# Sheet2.net
KiCad netlist of a schematic drawn in Altium Designer
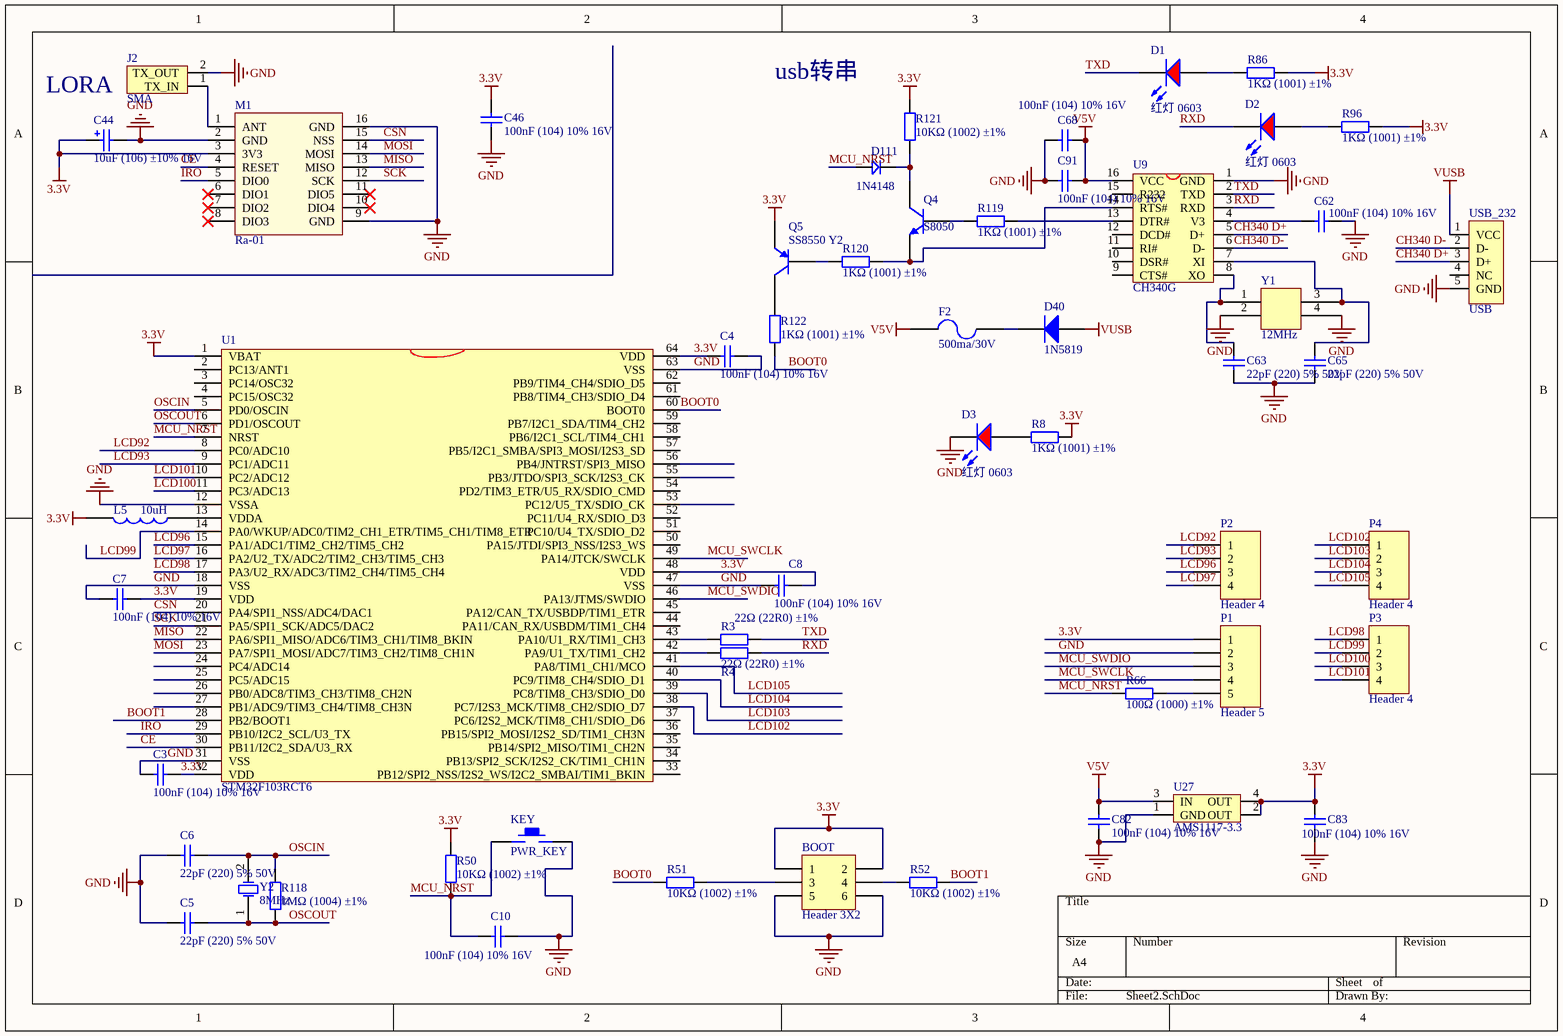
[diagram p0: Sheet2.SchDoc]

(export (version "E")
  (design (tool "Eeschema 10.0.6"))
  (components
    (comp (ref "BOOT")
      (value "Header 3X2")
      (footprint "HDR2X3")
      (description "Header, 3-Pin, Dual row")
      (fields (field (name "PUBLISHER") "Altium Limited"))
      (libsource (lib "WarShip V3 STM32103封装库") (part "Header 3X2"))
    )
    (comp (ref "C3")
      (value "100nF (104) 10% 16V")
      (footprint "0402_C")
      (description "贴片电容")
      (libsource (lib "Miscellaneous Devices LC") (part "0402 100nF (104) 10% 16V"))
    )
    (comp (ref "C4")
      (value "100nF (104) 10% 16V")
      (footprint "0402_C")
      (description "贴片电容")
      (libsource (lib "Miscellaneous Devices LC") (part "0402 100nF (104) 10% 16V"))
    )
    (comp (ref "C5")
      (value "22pF (220) 5% 50V")
      (footprint "0402_C")
      (description "贴片电容")
      (libsource (lib "Miscellaneous Devices LC") (part "0402 22pF (220) 5% 50V"))
    )
    (comp (ref "C6")
      (value "22pF (220) 5% 50V")
      (footprint "0402_C")
      (description "贴片电容")
      (libsource (lib "Miscellaneous Devices LC") (part "0402 22pF (220) 5% 50V"))
    )
    (comp (ref "C7")
      (value "100nF (104) 10% 16V")
      (footprint "0402_C")
      (description "贴片电容")
      (libsource (lib "Miscellaneous Devices LC") (part "0402 100nF (104) 10% 16V"))
    )
    (comp (ref "C8")
      (value "100nF (104) 10% 16V")
      (footprint "0402_C")
      (description "贴片电容")
      (libsource (lib "Miscellaneous Devices LC") (part "0402 100nF (104) 10% 16V"))
    )
    (comp (ref "C10")
      (value "100nF (104) 10% 16V")
      (footprint "0402_C")
      (description "贴片电容")
      (libsource (lib "Miscellaneous Devices LC") (part "0402 100nF (104) 10% 16V"))
    )
    (comp (ref "C44")
      (value "10uF (106) ±10% 16V")
      (footprint "CASE-A_3216")
      (description "钽电容")
      (libsource (lib "Miscellaneous Devices LC") (part "3216 10uF (106) 10% 16V"))
    )
    (comp (ref "C46")
      (value "100nF (104) 10% 16V")
      (footprint "0402_C")
      (description "贴片电容")
      (libsource (lib "Miscellaneous Devices LC") (part "0402 100nF (104) 10% 16V"))
    )
    (comp (ref "C62")
      (value "100nF (104) 10% 16V")
      (footprint "0402_C")
      (description "贴片电容")
      (libsource (lib "Miscellaneous Devices LC") (part "0402 100nF (104) 10% 16V"))
    )
    (comp (ref "C63")
      (value "22pF (220) 5% 50V")
      (footprint "0402_C")
      (description "贴片电容")
      (libsource (lib "Miscellaneous Devices LC") (part "0402 22pF (220) 5% 50V"))
    )
    (comp (ref "C65")
      (value "22pF (220) 5% 50V")
      (footprint "0402_C")
      (description "贴片电容")
      (libsource (lib "Miscellaneous Devices LC") (part "0402 22pF (220) 5% 50V"))
    )
    (comp (ref "C68")
      (value "100nF (104) 10% 16V")
      (footprint "0402_C")
      (description "贴片电容")
      (libsource (lib "Miscellaneous Devices LC") (part "0402 100nF (104) 10% 16V"))
    )
    (comp (ref "C82")
      (value "100nF (104) 10% 16V")
      (footprint "0402_C")
      (description "贴片电容")
      (libsource (lib "Miscellaneous Devices LC") (part "0402 100nF (104) 10% 16V"))
    )
    (comp (ref "C83")
      (value "100nF (104) 10% 16V")
      (footprint "0402_C")
      (description "贴片电容")
      (libsource (lib "Miscellaneous Devices LC") (part "0402 100nF (104) 10% 16V"))
    )
    (comp (ref "C91")
      (value "100nF (104) 10% 16V")
      (footprint "0402_C")
      (description "贴片电容")
      (libsource (lib "Miscellaneous Devices LC") (part "0402 100nF (104) 10% 16V"))
    )
    (comp (ref "D1")
      (value "红灯 0603")
      (footprint "0603_LED_S1")
      (description "发光二极管")
      (libsource (lib "Miscellaneous Devices LC") (part "0603 红灯"))
    )
    (comp (ref "D2")
      (value "红灯 0603")
      (footprint "0603_LED_S1")
      (description "发光二极管")
      (libsource (lib "Miscellaneous Devices LC") (part "0603 红灯"))
    )
    (comp (ref "D3")
      (value "红灯 0603")
      (footprint "0603_LED_S1")
      (description "发光二极管")
      (libsource (lib "Miscellaneous Devices LC") (part "0603 红灯"))
    )
    (comp (ref "D40")
      (value "1N5819")
      (footprint "LED-3528")
      (description "1 Amp General Purpose Rectifier")
      (fields (field (name "PUBLISHER") "Altium Limited"))
      (libsource (lib "*") (part "Diode 1N4001"))
    )
    (comp (ref "D111")
      (value "1N4148")
      (footprint "DIODE_SOP")
      (libsource (lib "WarShip V3 STM32103封装库") (part "D"))
    )
    (comp (ref "F2")
      (value "500ma/30V")
      (footprint "1812")
      (description "Fuse")
      (libsource (lib "*") (part "FUSE2"))
    )
    (comp (ref "J2")
      (value "SMA")
      (footprint "SMA-2")
      (description "SMA-2")
      (libsource (lib "ATK-SIM800C") (part "SMA-2"))
    )
    (comp (ref "KEY") (value "PWR_KEY") (libsource (lib "ATK-SIM800C") (part "KEY_M")))
    (comp (ref "L5") (value "10uH") (footprint "0805_L") (libsource (lib "*") (part "INDUCTOR1")))
    (comp (ref "M1")
      (value "Ra-01")
      (footprint "Ra-01 Module")
      (libsource (lib "Ra-01 Module") (part "Ra-01 Module"))
    )
    (comp (ref "P1")
      (value "Header 5")
      (footprint "HDR1X5")
      (description "Header, 5-Pin")
      (fields (field (name "PUBLISHER") "Altium Limited"))
      (libsource (lib "Miscellaneous Connectors") (part "Header 5"))
    )
    (comp (ref "P2")
      (value "Header 4")
      (footprint "HDR1X4")
      (description "Header, 4-Pin")
      (fields (field (name "PUBLISHER") "Altium Limited"))
      (libsource (lib "WarShip V3 STM32103封装库") (part "Header 4"))
    )
    (comp (ref "P3")
      (value "Header 4")
      (footprint "HDR1X4")
      (description "Header, 4-Pin")
      (fields (field (name "PUBLISHER") "Altium Limited"))
      (libsource (lib "WarShip V3 STM32103封装库") (part "Header 4"))
    )
    (comp (ref "P4")
      (value "Header 4")
      (footprint "HDR1X4")
      (description "Header, 4-Pin")
      (fields (field (name "PUBLISHER") "Altium Limited"))
      (libsource (lib "WarShip V3 STM32103封装库") (part "Header 4"))
    )
    (comp (ref "Q4")
      (value "S8050")
      (footprint "SOT-23R")
      (description "NPN Bipolar Transistor")
      (fields (field (name "PUBLISHER") "Altium Limited"))
      (libsource (lib "Miscellaneous Devices") (part "QNPN"))
    )
    (comp (ref "Q5")
      (value "SS8550 Y2")
      (footprint "SOT-23(SOT-23-3)")
      (description "三极管")
      (libsource (lib "Miscellaneous Devices LC") (part "SOT-23 SS8550 Y2"))
    )
    (comp (ref "R3")
      (value "22Ω (22R0) ±1%")
      (footprint "0402_R")
      (description "贴片电阻")
      (libsource (lib "Miscellaneous Devices LC") (part "0402 22Ω (22R0) 1%"))
    )
    (comp (ref "R4")
      (value "22Ω (22R0) ±1%")
      (footprint "0402_R")
      (description "贴片电阻")
      (libsource (lib "Miscellaneous Devices LC") (part "0402 22Ω (22R0) 1%"))
    )
    (comp (ref "R8")
      (value "1KΩ (1001) ±1%")
      (footprint "0402_R")
      (description "贴片电阻")
      (libsource (lib "Miscellaneous Devices LC") (part "0402 1KΩ (1001) 1%"))
    )
    (comp (ref "R50")
      (value "10KΩ (1002) ±1%")
      (footprint "0402_R")
      (description "贴片电阻")
      (libsource (lib "Miscellaneous Devices LC") (part "0402 10KΩ (1002) 1%"))
    )
    (comp (ref "R51")
      (value "10KΩ (1002) ±1%")
      (footprint "0402_R")
      (description "贴片电阻")
      (libsource (lib "") (part "0402 10KΩ (1002) 1%_1"))
    )
    (comp (ref "R52")
      (value "10KΩ (1002) ±1%")
      (footprint "0402_R")
      (description "贴片电阻")
      (libsource (lib "") (part "0402 10KΩ (1002) 1%_1"))
    )
    (comp (ref "R66")
      (value "100Ω (1000) ±1%")
      (footprint "0402_R")
      (description "贴片电阻")
      (libsource (lib "Miscellaneous Devices LC") (part "0402 100Ω (1000) 1%"))
    )
    (comp (ref "R86")
      (value "1KΩ (1001) ±1%")
      (footprint "0402_R")
      (description "贴片电阻")
      (libsource (lib "Miscellaneous Devices LC") (part "0402 1KΩ (1001) 1%"))
    )
    (comp (ref "R96")
      (value "1KΩ (1001) ±1%")
      (footprint "0402_R")
      (description "贴片电阻")
      (libsource (lib "Miscellaneous Devices LC") (part "0402 1KΩ (1001) 1%"))
    )
    (comp (ref "R118")
      (value "1MΩ (1004) ±1%")
      (footprint "0402_R")
      (description "贴片电阻")
      (libsource (lib "Miscellaneous Devices LC") (part "0402 1MΩ (1004) 1%"))
    )
    (comp (ref "R119")
      (value "1KΩ (1001) ±1%")
      (footprint "0402_R")
      (description "贴片电阻")
      (libsource (lib "Miscellaneous Devices LC") (part "0402 1KΩ (1001) 1%"))
    )
    (comp (ref "R120")
      (value "1KΩ (1001) ±1%")
      (footprint "0402_R")
      (description "贴片电阻")
      (libsource (lib "Miscellaneous Devices LC") (part "0402 1KΩ (1001) 1%"))
    )
    (comp (ref "R121")
      (value "10KΩ (1002) ±1%")
      (footprint "0402_R")
      (description "贴片电阻")
      (libsource (lib "Miscellaneous Devices LC") (part "0402 10KΩ (1002) 1%"))
    )
    (comp (ref "R122")
      (value "1KΩ (1001) ±1%")
      (footprint "0402_R")
      (description "贴片电阻")
      (libsource (lib "") (part "0402 1KΩ (1001) 1%_1"))
    )
    (comp (ref "U1")
      (value "STM32F103RCT6")
      (footprint "LQFP-64_10x10x05P")
      (libsource (lib "MiniSTM32 V3.0封装库") (part "STM32F103RDT6"))
    )
    (comp (ref "U9")
      (value "CH340G")
      (footprint "SOP16M")
      (description "USB2UART")
      (libsource (lib "阿波罗STM32F4&F7底板封装库") (part "CH340G"))
    )
    (comp (ref "U27")
      (value "AMS1117-3.3")
      (footprint "AMS1117")
      (libsource (lib "阿波罗STM32F4&F7底板封装库") (part "AMS1117"))
    )
    (comp (ref "USB_232")
      (value "USB")
      (footprint "USB（公）:PCBComponent_1")
      (libsource (lib "WarShip V3 STM32103封装库") (part "USB5"))
    )
    (comp (ref "Y1") (value "12MHz") (footprint "LC-SMD-3225_4P") (libsource (lib "晶振") (part "Component_1")))
    (comp (ref "Y2")
      (value "8MHz")
      (footprint "贴片晶振8mhz:PCBComponent_1")
      (description "Crystal Oscillator")
      (fields (field (name "PUBLISHER") "Altium Limited"))
      (libsource (lib "MiniSTM32 V3.0封装库") (part "XTAL"))
    )
  )
  (nets
    (net (code "1") (name "/BOOT0") (class "Default")
      (node (ref "R122") (pin "1") (pinfunction "1_1") (pintype "passive"))
      (node (ref "R51") (pin "2") (pinfunction "2_2") (pintype "passive"))
      (node (ref "U1") (pin "60") (pinfunction "BOOT0_60") (pintype "passive"))
    )
    (net (code "2") (name "/BOOT1") (class "Default")
      (node (ref "R52") (pin "1") (pinfunction "1_1") (pintype "passive"))
      (node (ref "U1") (pin "28") (pinfunction "PB2/BOOT1_28") (pintype "passive"))
    )
    (net (code "3") (name "/CE") (class "Default")
      (node (ref "M1") (pin "4") (pinfunction "RESET_4") (pintype "passive"))
      (node (ref "U1") (pin "30") (pinfunction "PB11/I2C2_SDA/U3_RX_30") (pintype "passive"))
    )
    (net (code "4") (name "/CH340 D+") (class "Default")
      (node (ref "U9") (pin "5") (pinfunction "D+_5") (pintype "passive"))
      (node (ref "USB_232") (pin "3") (pinfunction "D+_3") (pintype "passive"))
    )
    (net (code "5") (name "/CH340 D-") (class "Default")
      (node (ref "U9") (pin "6") (pinfunction "D-_6") (pintype "passive"))
      (node (ref "USB_232") (pin "2") (pinfunction "D-_2") (pintype "passive"))
    )
    (net (code "6") (name "/CSN") (class "Default")
      (node (ref "M1") (pin "15") (pinfunction "NSS_15") (pintype "passive"))
      (node (ref "U1") (pin "20") (pinfunction "PA4/SPI1_NSS/ADC4/DAC1_20") (pintype "passive"))
    )
    (net (code "7") (name "/IRO") (class "Default")
      (node (ref "M1") (pin "5") (pinfunction "DIO0_5") (pintype "passive"))
      (node (ref "U1") (pin "29") (pinfunction "PB10/I2C2_SCL/U3_TX_29") (pintype "passive"))
    )
    (net (code "8") (name "/LCD92") (class "Default")
      (node (ref "P2") (pin "1") (pinfunction "1_1") (pintype "passive"))
      (node (ref "U1") (pin "8") (pinfunction "PC0/ADC10_8") (pintype "passive"))
    )
    (net (code "9") (name "/LCD93") (class "Default")
      (node (ref "P2") (pin "2") (pinfunction "2_2") (pintype "passive"))
      (node (ref "U1") (pin "9") (pinfunction "PC1/ADC11_9") (pintype "passive"))
    )
    (net (code "10") (name "/LCD96") (class "Default")
      (node (ref "P2") (pin "3") (pinfunction "3_3") (pintype "passive"))
      (node (ref "U1") (pin "15") (pinfunction "PA1/ADC1/TIM2_CH2/TIM5_CH2_15") (pintype "passive"))
    )
    (net (code "11") (name "/LCD97") (class "Default")
      (node (ref "P2") (pin "4") (pinfunction "4_4") (pintype "passive"))
      (node (ref "U1") (pin "16") (pinfunction "PA2/U2_TX/ADC2/TIM2_CH3/TIM5_CH3_16") (pintype "passive"))
    )
    (net (code "12") (name "/LCD98") (class "Default")
      (node (ref "P3") (pin "1") (pinfunction "1_1") (pintype "passive"))
      (node (ref "U1") (pin "17") (pinfunction "PA3/U2_RX/ADC3/TIM2_CH4/TIM5_CH4_17") (pintype "passive"))
    )
    (net (code "13") (name "/LCD99") (class "Default")
      (node (ref "P3") (pin "2") (pinfunction "2_2") (pintype "passive"))
      (node (ref "U1") (pin "14") (pinfunction "PA0/WKUP/ADC0/TIM2_CH1_ETR/TIM5_CH1/TIM8_ETR_14") (pintype "passive"))
    )
    (net (code "14") (name "/LCD100") (class "Default")
      (node (ref "P3") (pin "3") (pinfunction "3_3") (pintype "passive"))
      (node (ref "U1") (pin "11") (pinfunction "PC3/ADC13_11") (pintype "passive"))
    )
    (net (code "15") (name "/LCD101") (class "Default")
      (node (ref "P3") (pin "4") (pinfunction "4_4") (pintype "passive"))
      (node (ref "U1") (pin "10") (pinfunction "PC2/ADC12_10") (pintype "passive"))
    )
    (net (code "16") (name "/LCD102") (class "Default")
      (node (ref "P4") (pin "1") (pinfunction "1_1") (pintype "passive"))
      (node (ref "U1") (pin "38") (pinfunction "PC7/I2S3_MCK/TIM8_CH2/SDIO_D7_38") (pintype "passive"))
    )
    (net (code "17") (name "/LCD103") (class "Default")
      (node (ref "P4") (pin "2") (pinfunction "2_2") (pintype "passive"))
      (node (ref "U1") (pin "39") (pinfunction "PC8/TIM8_CH3/SDIO_D0_39") (pintype "passive"))
    )
    (net (code "18") (name "/LCD104") (class "Default")
      (node (ref "P4") (pin "3") (pinfunction "3_3") (pintype "passive"))
      (node (ref "U1") (pin "40") (pinfunction "PC9/TIM8_CH4/SDIO_D1_40") (pintype "passive"))
    )
    (net (code "19") (name "/LCD105") (class "Default")
      (node (ref "P4") (pin "4") (pinfunction "4_4") (pintype "passive"))
      (node (ref "U1") (pin "41") (pinfunction "PA8/TIM1_CH1/MCO_41") (pintype "passive"))
    )
    (net (code "20") (name "/MCU_NRST") (class "Default")
      (node (ref "C10") (pin "1") (pinfunction "1_1") (pintype "passive"))
      (node (ref "D111") (pin "1") (pintype "passive"))
      (node (ref "KEY") (pin "1") (pinfunction "1_1") (pintype "passive"))
      (node (ref "R50") (pin "1") (pinfunction "1_1") (pintype "passive"))
      (node (ref "R66") (pin "1") (pinfunction "1_1") (pintype "passive"))
      (node (ref "U1") (pin "7") (pinfunction "NRST_7") (pintype "passive"))
    )
    (net (code "21") (name "/MCU_SWCLK") (class "Default")
      (node (ref "P1") (pin "4") (pinfunction "4_4") (pintype "passive"))
      (node (ref "U1") (pin "49") (pinfunction "PA14/JTCK/SWCLK_49") (pintype "passive"))
    )
    (net (code "22") (name "/MCU_SWDIO") (class "Default")
      (node (ref "P1") (pin "3") (pinfunction "3_3") (pintype "passive"))
      (node (ref "U1") (pin "46") (pinfunction "PA13/JTMS/SWDIO_46") (pintype "passive"))
    )
    (net (code "23") (name "/MISO") (class "Default")
      (node (ref "M1") (pin "13") (pinfunction "MISO_13") (pintype "passive"))
      (node (ref "U1") (pin "22") (pinfunction "PA6/SPI1_MISO/ADC6/TIM3_CH1/TIM8_BKIN_22") (pintype "passive"))
    )
    (net (code "24") (name "/MOSI") (class "Default")
      (node (ref "M1") (pin "14") (pinfunction "MOSI_14") (pintype "passive"))
      (node (ref "U1") (pin "23") (pinfunction "PA7/SPI1_MOSI/ADC7/TIM3_CH2/TIM8_CH1N_23") (pintype "passive"))
    )
    (net (code "25") (name "/OSCIN") (class "Default")
      (node (ref "C6") (pin "1") (pinfunction "1_1") (pintype "passive"))
      (node (ref "R118") (pin "2") (pinfunction "2_2") (pintype "passive"))
      (node (ref "U1") (pin "5") (pinfunction "PD0/OSCIN_5") (pintype "passive"))
      (node (ref "Y2") (pin "2") (pinfunction "OSC2_2") (pintype "passive"))
    )
    (net (code "26") (name "/OSCOUT") (class "Default")
      (node (ref "C5") (pin "1") (pinfunction "1_1") (pintype "passive"))
      (node (ref "R118") (pin "1") (pinfunction "1_1") (pintype "passive"))
      (node (ref "U1") (pin "6") (pinfunction "PD1/OSCOUT_6") (pintype "passive"))
      (node (ref "Y2") (pin "1") (pinfunction "OSC1_1") (pintype "passive"))
    )
    (net (code "27") (name "/RXD") (class "Default")
      (node (ref "D2") (pin "K") (pinfunction "K_K") (pintype "passive"))
      (node (ref "R4") (pin "2") (pinfunction "2_2") (pintype "passive"))
      (node (ref "U9") (pin "3") (pinfunction "RXD_3") (pintype "passive"))
    )
    (net (code "28") (name "/SCK") (class "Default")
      (node (ref "M1") (pin "12") (pinfunction "SCK_12") (pintype "passive"))
      (node (ref "U1") (pin "21") (pinfunction "PA5/SPI1_SCK/ADC5/DAC2_21") (pintype "passive"))
    )
    (net (code "29") (name "/TXD") (class "Default")
      (node (ref "D1") (pin "K") (pinfunction "K_K") (pintype "passive"))
      (node (ref "R3") (pin "2") (pinfunction "2_2") (pintype "passive"))
      (node (ref "U9") (pin "2") (pinfunction "TXD_2") (pintype "passive"))
    )
    (net (code "30") (name "3.3V") (class "Default")
      (node (ref "BOOT") (pin "1") (pinfunction "1_1") (pintype "passive"))
      (node (ref "BOOT") (pin "2") (pinfunction "2_2") (pintype "passive"))
      (node (ref "C3") (pin "2") (pinfunction "2_2") (pintype "passive"))
      (node (ref "C4") (pin "1") (pinfunction "1_1") (pintype "passive"))
      (node (ref "C44") (pin "1") (pinfunction "1_1") (pintype "passive"))
      (node (ref "C46") (pin "2") (pinfunction "2_2") (pintype "passive"))
      (node (ref "C7") (pin "2") (pinfunction "2_2") (pintype "passive"))
      (node (ref "C8") (pin "2") (pinfunction "2_2") (pintype "passive"))
      (node (ref "C83") (pin "2") (pinfunction "2_2") (pintype "passive"))
      (node (ref "L5") (pin "1") (pinfunction "1_1") (pintype "passive"))
      (node (ref "M1") (pin "3") (pinfunction "3V3_3") (pintype "passive"))
      (node (ref "P1") (pin "1") (pinfunction "1_1") (pintype "passive"))
      (node (ref "Q5") (pin "2") (pinfunction "E_2") (pintype "passive"))
      (node (ref "R121") (pin "2") (pinfunction "2_2") (pintype "passive"))
      (node (ref "R50") (pin "2") (pinfunction "2_2") (pintype "passive"))
      (node (ref "R8") (pin "2") (pinfunction "2_2") (pintype "passive"))
      (node (ref "R86") (pin "2") (pinfunction "2_2") (pintype "passive"))
      (node (ref "R96") (pin "2") (pinfunction "2_2") (pintype "passive"))
      (node (ref "U1") (pin "1") (pinfunction "VBAT_1") (pintype "passive"))
      (node (ref "U1") (pin "19") (pinfunction "VDD_19") (pintype "passive"))
      (node (ref "U1") (pin "32") (pinfunction "VDD_32") (pintype "passive"))
      (node (ref "U1") (pin "48") (pinfunction "VDD_48") (pintype "passive"))
      (node (ref "U1") (pin "64") (pinfunction "VDD_64") (pintype "passive"))
      (node (ref "U27") (pin "2") (pinfunction "OUT_2") (pintype "passive"))
      (node (ref "U27") (pin "4") (pinfunction "OUT_4") (pintype "passive"))
    )
    (net (code "31") (name "GND") (class "Default")
      (node (ref "BOOT") (pin "5") (pinfunction "5_5") (pintype "passive"))
      (node (ref "BOOT") (pin "6") (pinfunction "6_6") (pintype "passive"))
      (node (ref "C10") (pin "2") (pinfunction "2_2") (pintype "passive"))
      (node (ref "C3") (pin "1") (pinfunction "1_1") (pintype "passive"))
      (node (ref "C4") (pin "2") (pinfunction "2_2") (pintype "passive"))
      (node (ref "C44") (pin "2") (pinfunction "2_2") (pintype "passive"))
      (node (ref "C46") (pin "1") (pinfunction "1_1") (pintype "passive"))
      (node (ref "C5") (pin "2") (pinfunction "2_2") (pintype "passive"))
      (node (ref "C6") (pin "2") (pinfunction "2_2") (pintype "passive"))
      (node (ref "C62") (pin "2") (pinfunction "2_2") (pintype "passive"))
      (node (ref "C63") (pin "1") (pinfunction "1_1") (pintype "passive"))
      (node (ref "C65") (pin "1") (pinfunction "1_1") (pintype "passive"))
      (node (ref "C68") (pin "1") (pinfunction "1_1") (pintype "passive"))
      (node (ref "C7") (pin "1") (pinfunction "1_1") (pintype "passive"))
      (node (ref "C8") (pin "1") (pinfunction "1_1") (pintype "passive"))
      (node (ref "C82") (pin "1") (pinfunction "1_1") (pintype "passive"))
      (node (ref "C83") (pin "1") (pinfunction "1_1") (pintype "passive"))
      (node (ref "C91") (pin "1") (pinfunction "1_1") (pintype "passive"))
      (node (ref "D3") (pin "K") (pinfunction "K_K") (pintype "passive"))
      (node (ref "J2") (pin "2") (pinfunction "TX_OUT_2") (pintype "passive"))
      (node (ref "KEY") (pin "2") (pinfunction "2_2") (pintype "passive"))
      (node (ref "M1") (pin "16") (pinfunction "GND_16") (pintype "passive"))
      (node (ref "M1") (pin "2") (pinfunction "GND_2") (pintype "passive"))
      (node (ref "M1") (pin "9") (pinfunction "GND_9") (pintype "passive"))
      (node (ref "P1") (pin "2") (pinfunction "2_2") (pintype "passive"))
      (node (ref "U1") (pin "12") (pinfunction "VSSA_12") (pintype "passive"))
      (node (ref "U1") (pin "18") (pinfunction "VSS_18") (pintype "passive"))
      (node (ref "U1") (pin "31") (pinfunction "VSS_31") (pintype "passive"))
      (node (ref "U1") (pin "47") (pinfunction "VSS_47") (pintype "passive"))
      (node (ref "U1") (pin "63") (pinfunction "VSS_63") (pintype "passive"))
      (node (ref "U27") (pin "1") (pinfunction "GND_1") (pintype "passive"))
      (node (ref "U9") (pin "1") (pinfunction "GND_1") (pintype "passive"))
      (node (ref "USB_232") (pin "5") (pinfunction "GND_5") (pintype "passive"))
      (node (ref "Y1") (pin "2") (pinfunction "2_2") (pintype "passive"))
      (node (ref "Y1") (pin "4") (pinfunction "4_4") (pintype "passive"))
    )
    (net (code "32") (name "Net-(BOOT-Pad3)") (class "Default")
      (node (ref "BOOT") (pin "3") (pinfunction "3_3") (pintype "passive"))
      (node (ref "R51") (pin "1") (pinfunction "1_1") (pintype "passive"))
    )
    (net (code "33") (name "Net-(BOOT-Pad4)") (class "Default")
      (node (ref "BOOT") (pin "4") (pinfunction "4_4") (pintype "passive"))
      (node (ref "R52") (pin "2") (pinfunction "2_2") (pintype "passive"))
    )
    (net (code "34") (name "Net-(D1-PadA)") (class "Default")
      (node (ref "D1") (pin "A") (pinfunction "A_A") (pintype "passive"))
      (node (ref "R86") (pin "1") (pinfunction "1_1") (pintype "passive"))
    )
    (net (code "35") (name "Net-(D2-PadA)") (class "Default")
      (node (ref "D2") (pin "A") (pinfunction "A_A") (pintype "passive"))
      (node (ref "R96") (pin "1") (pinfunction "1_1") (pintype "passive"))
    )
    (net (code "36") (name "Net-(D3-PadA)") (class "Default")
      (node (ref "D3") (pin "A") (pinfunction "A_A") (pintype "passive"))
      (node (ref "R8") (pin "1") (pinfunction "1_1") (pintype "passive"))
    )
    (net (code "37") (name "Net-(D40-K)") (class "Default")
      (node (ref "D40") (pin "2") (pinfunction "K_2") (pintype "passive"))
      (node (ref "F2") (pin "2") (pinfunction "2_2") (pintype "passive"))
    )
    (net (code "38") (name "Net-(J2-TX_IN)") (class "Default")
      (node (ref "J2") (pin "1") (pinfunction "TX_IN_1") (pintype "passive"))
      (node (ref "M1") (pin "1") (pinfunction "ANT_1") (pintype "passive"))
    )
    (net (code "39") (name "Net-(P1-Pad5)") (class "Default")
      (node (ref "P1") (pin "5") (pinfunction "5_5") (pintype "passive"))
      (node (ref "R66") (pin "2") (pinfunction "2_2") (pintype "passive"))
    )
    (net (code "40") (name "Net-(Q4-B)") (class "Default")
      (node (ref "Q4") (pin "2") (pinfunction "B_2") (pintype "passive"))
      (node (ref "R119") (pin "1") (pinfunction "1_1") (pintype "passive"))
    )
    (net (code "41") (name "Net-(Q4-C)") (class "Default")
      (node (ref "D111") (pin "2") (pintype "passive"))
      (node (ref "Q4") (pin "1") (pinfunction "C_1") (pintype "passive"))
      (node (ref "R121") (pin "1") (pinfunction "1_1") (pintype "passive"))
    )
    (net (code "42") (name "Net-(Q4-E)") (class "Default")
      (node (ref "Q4") (pin "3") (pinfunction "E_3") (pintype "passive"))
      (node (ref "R120") (pin "2") (pinfunction "2_2") (pintype "passive"))
      (node (ref "U9") (pin "14") (pinfunction "RTS#_14") (pintype "passive"))
    )
    (net (code "43") (name "Net-(Q5-B)") (class "Default")
      (node (ref "Q5") (pin "1") (pinfunction "B_1") (pintype "passive"))
      (node (ref "R120") (pin "1") (pinfunction "1_1") (pintype "passive"))
    )
    (net (code "44") (name "Net-(Q5-C)") (class "Default")
      (node (ref "Q5") (pin "3") (pinfunction "C_3") (pintype "passive"))
      (node (ref "R122") (pin "2") (pinfunction "2_2") (pintype "passive"))
    )
    (net (code "45") (name "Net-(U1-PA9{slash}U1_TX{slash}TIM1_CH2)") (class "Default")
      (node (ref "R4") (pin "1") (pinfunction "1_1") (pintype "passive"))
      (node (ref "U1") (pin "42") (pinfunction "PA9/U1_TX/TIM1_CH2_42") (pintype "passive"))
    )
    (net (code "46") (name "Net-(U1-PA10{slash}U1_RX{slash}TIM1_CH3)") (class "Default")
      (node (ref "R3") (pin "1") (pinfunction "1_1") (pintype "passive"))
      (node (ref "U1") (pin "43") (pinfunction "PA10/U1_RX/TIM1_CH3_43") (pintype "passive"))
    )
    (net (code "47") (name "Net-(U1-VDDA)") (class "Default")
      (node (ref "L5") (pin "2") (pinfunction "2_2") (pintype "passive"))
      (node (ref "U1") (pin "13") (pinfunction "VDDA_13") (pintype "passive"))
    )
    (net (code "48") (name "Net-(U9-DTR#)") (class "Default")
      (node (ref "R119") (pin "2") (pinfunction "2_2") (pintype "passive"))
      (node (ref "U9") (pin "13") (pinfunction "DTR#_13") (pintype "passive"))
    )
    (net (code "49") (name "Net-(U9-V3)") (class "Default")
      (node (ref "C62") (pin "1") (pinfunction "1_1") (pintype "passive"))
      (node (ref "U9") (pin "4") (pinfunction "V3_4") (pintype "passive"))
    )
    (net (code "50") (name "Net-(U9-XI)") (class "Default")
      (node (ref "C65") (pin "2") (pinfunction "2_2") (pintype "passive"))
      (node (ref "U9") (pin "7") (pinfunction "XI_7") (pintype "passive"))
      (node (ref "Y1") (pin "3") (pinfunction "3_3") (pintype "passive"))
    )
    (net (code "51") (name "Net-(U9-XO)") (class "Default")
      (node (ref "C63") (pin "2") (pinfunction "2_2") (pintype "passive"))
      (node (ref "U9") (pin "8") (pinfunction "XO_8") (pintype "passive"))
      (node (ref "Y1") (pin "1") (pinfunction "1_1") (pintype "passive"))
    )
    (net (code "52") (name "V5V") (class "Default")
      (node (ref "C68") (pin "2") (pinfunction "2_2") (pintype "passive"))
      (node (ref "C82") (pin "2") (pinfunction "2_2") (pintype "passive"))
      (node (ref "C91") (pin "2") (pinfunction "2_2") (pintype "passive"))
      (node (ref "F2") (pin "1") (pinfunction "1_1") (pintype "passive"))
      (node (ref "U27") (pin "3") (pinfunction "IN_3") (pintype "passive"))
      (node (ref "U9") (pin "16") (pinfunction "VCC_16") (pintype "passive"))
    )
    (net (code "53") (name "VUSB") (class "Default")
      (node (ref "D40") (pin "1") (pinfunction "A_1") (pintype "passive"))
      (node (ref "USB_232") (pin "1") (pinfunction "VCC_1") (pintype "passive"))
    )
    (net (code "54") (name "unconnected-(M1-DIO1-Pad6)") (class "Default")
      (node (ref "M1") (pin "6") (pinfunction "DIO1_6") (pintype "passive+no_connect"))
    )
    (net (code "55") (name "unconnected-(M1-DIO2-Pad7)") (class "Default")
      (node (ref "M1") (pin "7") (pinfunction "DIO2_7") (pintype "passive+no_connect"))
    )
    (net (code "56") (name "unconnected-(M1-DIO3-Pad8)") (class "Default")
      (node (ref "M1") (pin "8") (pinfunction "DIO3_8") (pintype "passive+no_connect"))
    )
    (net (code "57") (name "unconnected-(M1-DIO4-Pad10)") (class "Default")
      (node (ref "M1") (pin "10") (pinfunction "DIO4_10") (pintype "passive+no_connect"))
    )
    (net (code "58") (name "unconnected-(M1-DIO5-Pad11)") (class "Default")
      (node (ref "M1") (pin "11") (pinfunction "DIO5_11") (pintype "passive+no_connect"))
    )
    (net (code "59") (name "unconnected-(U1-PA11{slash}CAN_RX{slash}USBDM{slash}TIM1_CH4-Pad44)") (class "Default")
      (node (ref "U1") (pin "44") (pinfunction "PA11/CAN_RX/USBDM/TIM1_CH4_44") (pintype "passive"))
    )
    (net (code "60") (name "unconnected-(U1-PA12{slash}CAN_TX{slash}USBDP{slash}TIM1_ETR-Pad45)") (class "Default")
      (node (ref "U1") (pin "45") (pinfunction "PA12/CAN_TX/USBDP/TIM1_ETR_45") (pintype "passive"))
    )
    (net (code "61") (name "unconnected-(U1-PA15{slash}JTDI{slash}SPI3_NSS{slash}I2S3_WS-Pad50)") (class "Default")
      (node (ref "U1") (pin "50") (pinfunction "PA15/JTDI/SPI3_NSS/I2S3_WS_50") (pintype "passive"))
    )
    (net (code "62") (name "unconnected-(U1-PB0{slash}ADC8{slash}TIM3_CH3{slash}TIM8_CH2N-Pad26)") (class "Default")
      (node (ref "U1") (pin "26") (pinfunction "PB0/ADC8/TIM3_CH3/TIM8_CH2N_26") (pintype "passive"))
    )
    (net (code "63") (name "unconnected-(U1-PB1{slash}ADC9{slash}TIM3_CH4{slash}TIM8_CH3N-Pad27)") (class "Default")
      (node (ref "U1") (pin "27") (pinfunction "PB1/ADC9/TIM3_CH4/TIM8_CH3N_27") (pintype "passive"))
    )
    (net (code "64") (name "unconnected-(U1-PB3{slash}JTDO{slash}SPI3_SCK{slash}I2S3_CK-Pad55)") (class "Default")
      (node (ref "U1") (pin "55") (pinfunction "PB3/JTDO/SPI3_SCK/I2S3_CK_55") (pintype "passive"))
    )
    (net (code "65") (name "unconnected-(U1-PB4{slash}JNTRST{slash}SPI3_MISO-Pad56)") (class "Default")
      (node (ref "U1") (pin "56") (pinfunction "PB4/JNTRST/SPI3_MISO_56") (pintype "passive"))
    )
    (net (code "66") (name "unconnected-(U1-PB5{slash}I2C1_SMBA{slash}SPI3_MOSI{slash}I2S3_SD-Pad57)") (class "Default")
      (node (ref "U1") (pin "57") (pinfunction "PB5/I2C1_SMBA/SPI3_MOSI/I2S3_SD_57") (pintype "passive"))
    )
    (net (code "67") (name "unconnected-(U1-PB6{slash}I2C1_SCL{slash}TIM4_CH1-Pad58)") (class "Default")
      (node (ref "U1") (pin "58") (pinfunction "PB6/I2C1_SCL/TIM4_CH1_58") (pintype "passive"))
    )
    (net (code "68") (name "unconnected-(U1-PB7{slash}I2C1_SDA{slash}TIM4_CH2-Pad59)") (class "Default")
      (node (ref "U1") (pin "59") (pinfunction "PB7/I2C1_SDA/TIM4_CH2_59") (pintype "passive"))
    )
    (net (code "69") (name "unconnected-(U1-PB8{slash}TIM4_CH3{slash}SDIO_D4-Pad61)") (class "Default")
      (node (ref "U1") (pin "61") (pinfunction "PB8/TIM4_CH3/SDIO_D4_61") (pintype "passive"))
    )
    (net (code "70") (name "unconnected-(U1-PB9{slash}TIM4_CH4{slash}SDIO_D5-Pad62)") (class "Default")
      (node (ref "U1") (pin "62") (pinfunction "PB9/TIM4_CH4/SDIO_D5_62") (pintype "passive"))
    )
    (net (code "71") (name "unconnected-(U1-PB12{slash}SPI2_NSS{slash}I2S2_WS{slash}I2C2_SMBAI{slash}TIM1_BKIN-Pad33)") (class "Default")
      (node (ref "U1") (pin "33") (pinfunction "PB12/SPI2_NSS/I2S2_WS/I2C2_SMBAI/TIM1_BKIN_33") (pintype "passive"))
    )
    (net (code "72") (name "unconnected-(U1-PB13{slash}SPI2_SCK{slash}I2S2_CK{slash}TIM1_CH1N-Pad34)") (class "Default")
      (node (ref "U1") (pin "34") (pinfunction "PB13/SPI2_SCK/I2S2_CK/TIM1_CH1N_34") (pintype "passive"))
    )
    (net (code "73") (name "unconnected-(U1-PB14{slash}SPI2_MISO{slash}TIM1_CH2N-Pad35)") (class "Default")
      (node (ref "U1") (pin "35") (pinfunction "PB14/SPI2_MISO/TIM1_CH2N_35") (pintype "passive"))
    )
    (net (code "74") (name "unconnected-(U1-PB15{slash}SPI2_MOSI{slash}I2S2_SD{slash}TIM1_CH3N-Pad36)") (class "Default")
      (node (ref "U1") (pin "36") (pinfunction "PB15/SPI2_MOSI/I2S2_SD/TIM1_CH3N_36") (pintype "passive"))
    )
    (net (code "75") (name "unconnected-(U1-PC4{slash}ADC14-Pad24)") (class "Default")
      (node (ref "U1") (pin "24") (pinfunction "PC4/ADC14_24") (pintype "passive"))
    )
    (net (code "76") (name "unconnected-(U1-PC5{slash}ADC15-Pad25)") (class "Default")
      (node (ref "U1") (pin "25") (pinfunction "PC5/ADC15_25") (pintype "passive"))
    )
    (net (code "77") (name "unconnected-(U1-PC6{slash}I2S2_MCK{slash}TIM8_CH1{slash}SDIO_D6-Pad37)") (class "Default")
      (node (ref "U1") (pin "37") (pinfunction "PC6/I2S2_MCK/TIM8_CH1/SDIO_D6_37") (pintype "passive"))
    )
    (net (code "78") (name "unconnected-(U1-PC10{slash}U4_TX{slash}SDIO_D2-Pad51)") (class "Default")
      (node (ref "U1") (pin "51") (pinfunction "PC10/U4_TX/SDIO_D2_51") (pintype "passive"))
    )
    (net (code "79") (name "unconnected-(U1-PC11{slash}U4_RX{slash}SDIO_D3-Pad52)") (class "Default")
      (node (ref "U1") (pin "52") (pinfunction "PC11/U4_RX/SDIO_D3_52") (pintype "passive"))
    )
    (net (code "80") (name "unconnected-(U1-PC12{slash}U5_TX{slash}SDIO_CK-Pad53)") (class "Default")
      (node (ref "U1") (pin "53") (pinfunction "PC12/U5_TX/SDIO_CK_53") (pintype "passive"))
    )
    (net (code "81") (name "unconnected-(U1-PC13{slash}ANT1-Pad2)") (class "Default")
      (node (ref "U1") (pin "2") (pinfunction "PC13/ANT1_2") (pintype "passive"))
    )
    (net (code "82") (name "unconnected-(U1-PC14{slash}OSC32-Pad3)") (class "Default")
      (node (ref "U1") (pin "3") (pinfunction "PC14/OSC32_3") (pintype "passive"))
    )
    (net (code "83") (name "unconnected-(U1-PC15{slash}OSC32-Pad4)") (class "Default")
      (node (ref "U1") (pin "4") (pinfunction "PC15/OSC32_4") (pintype "passive"))
    )
    (net (code "84") (name "unconnected-(U1-PD2{slash}TIM3_ETR{slash}U5_RX{slash}SDIO_CMD-Pad54)") (class "Default")
      (node (ref "U1") (pin "54") (pinfunction "PD2/TIM3_ETR/U5_RX/SDIO_CMD_54") (pintype "passive"))
    )
    (net (code "85") (name "unconnected-(U9-CTS#-Pad9)") (class "Default")
      (node (ref "U9") (pin "9") (pinfunction "CTS#_9") (pintype "passive"))
    )
    (net (code "86") (name "unconnected-(U9-DCD#-Pad12)") (class "Default")
      (node (ref "U9") (pin "12") (pinfunction "DCD#_12") (pintype "passive"))
    )
    (net (code "87") (name "unconnected-(U9-DSR#-Pad10)") (class "Default")
      (node (ref "U9") (pin "10") (pinfunction "DSR#_10") (pintype "passive"))
    )
    (net (code "88") (name "unconnected-(U9-R232-Pad15)") (class "Default")
      (node (ref "U9") (pin "15") (pinfunction "R232_15") (pintype "passive"))
    )
    (net (code "89") (name "unconnected-(U9-RI#-Pad11)") (class "Default")
      (node (ref "U9") (pin "11") (pinfunction "RI#_11") (pintype "passive"))
    )
    (net (code "90") (name "unconnected-(USB_232-NC-Pad4)") (class "Default")
      (node (ref "USB_232") (pin "4") (pinfunction "NC_4") (pintype "passive"))
    )
  )
)
